# Calciatore_Rev_2_UP.net
KiCad netlist of a schematic drawn in EAGLE
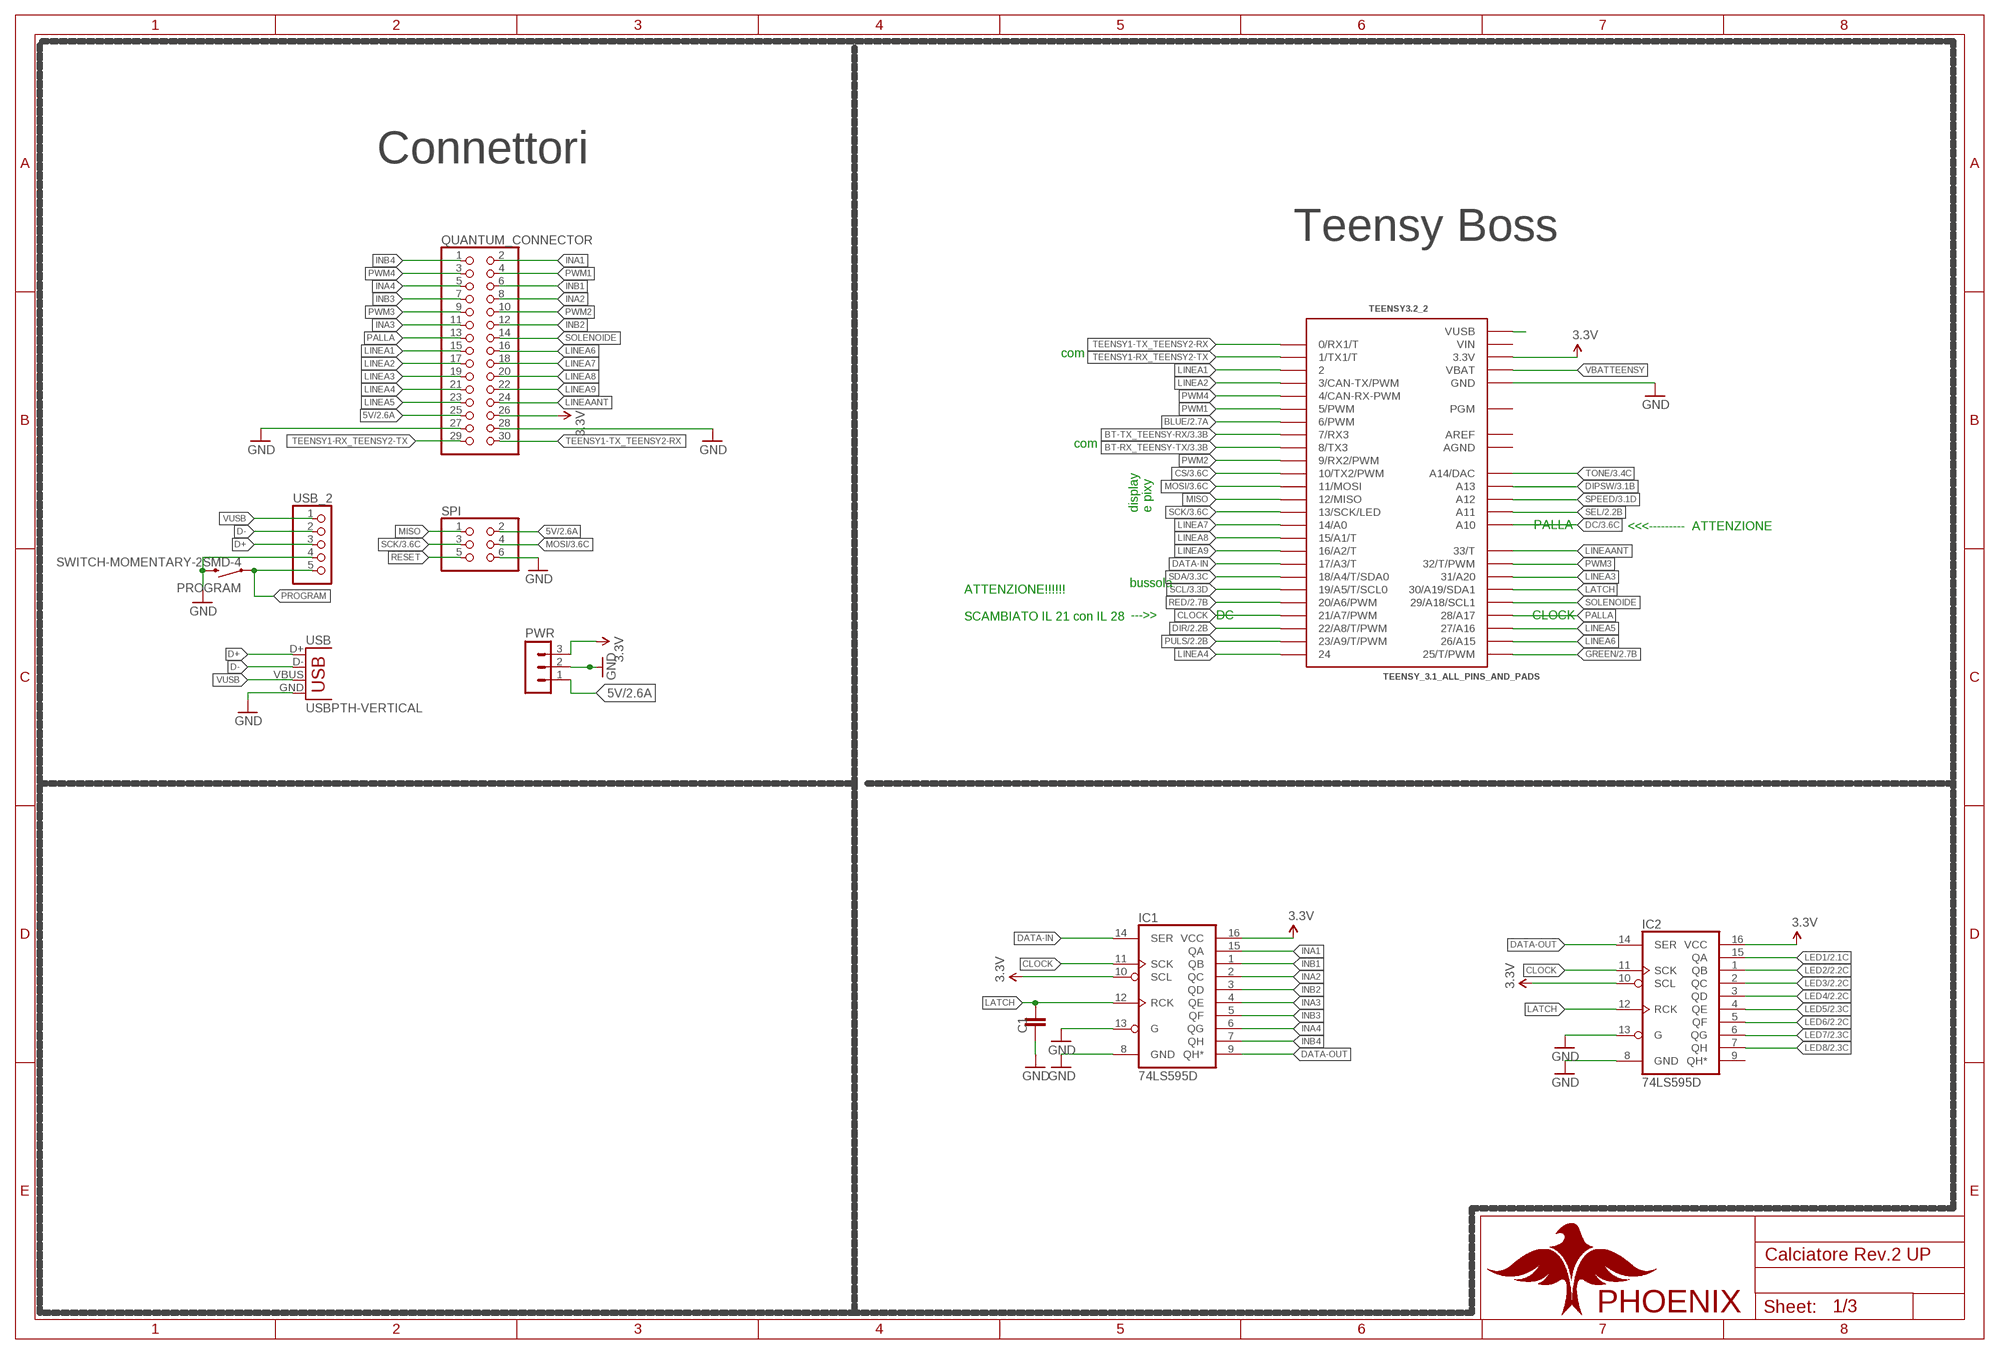
[diagram p0: schematic, sheet 1]
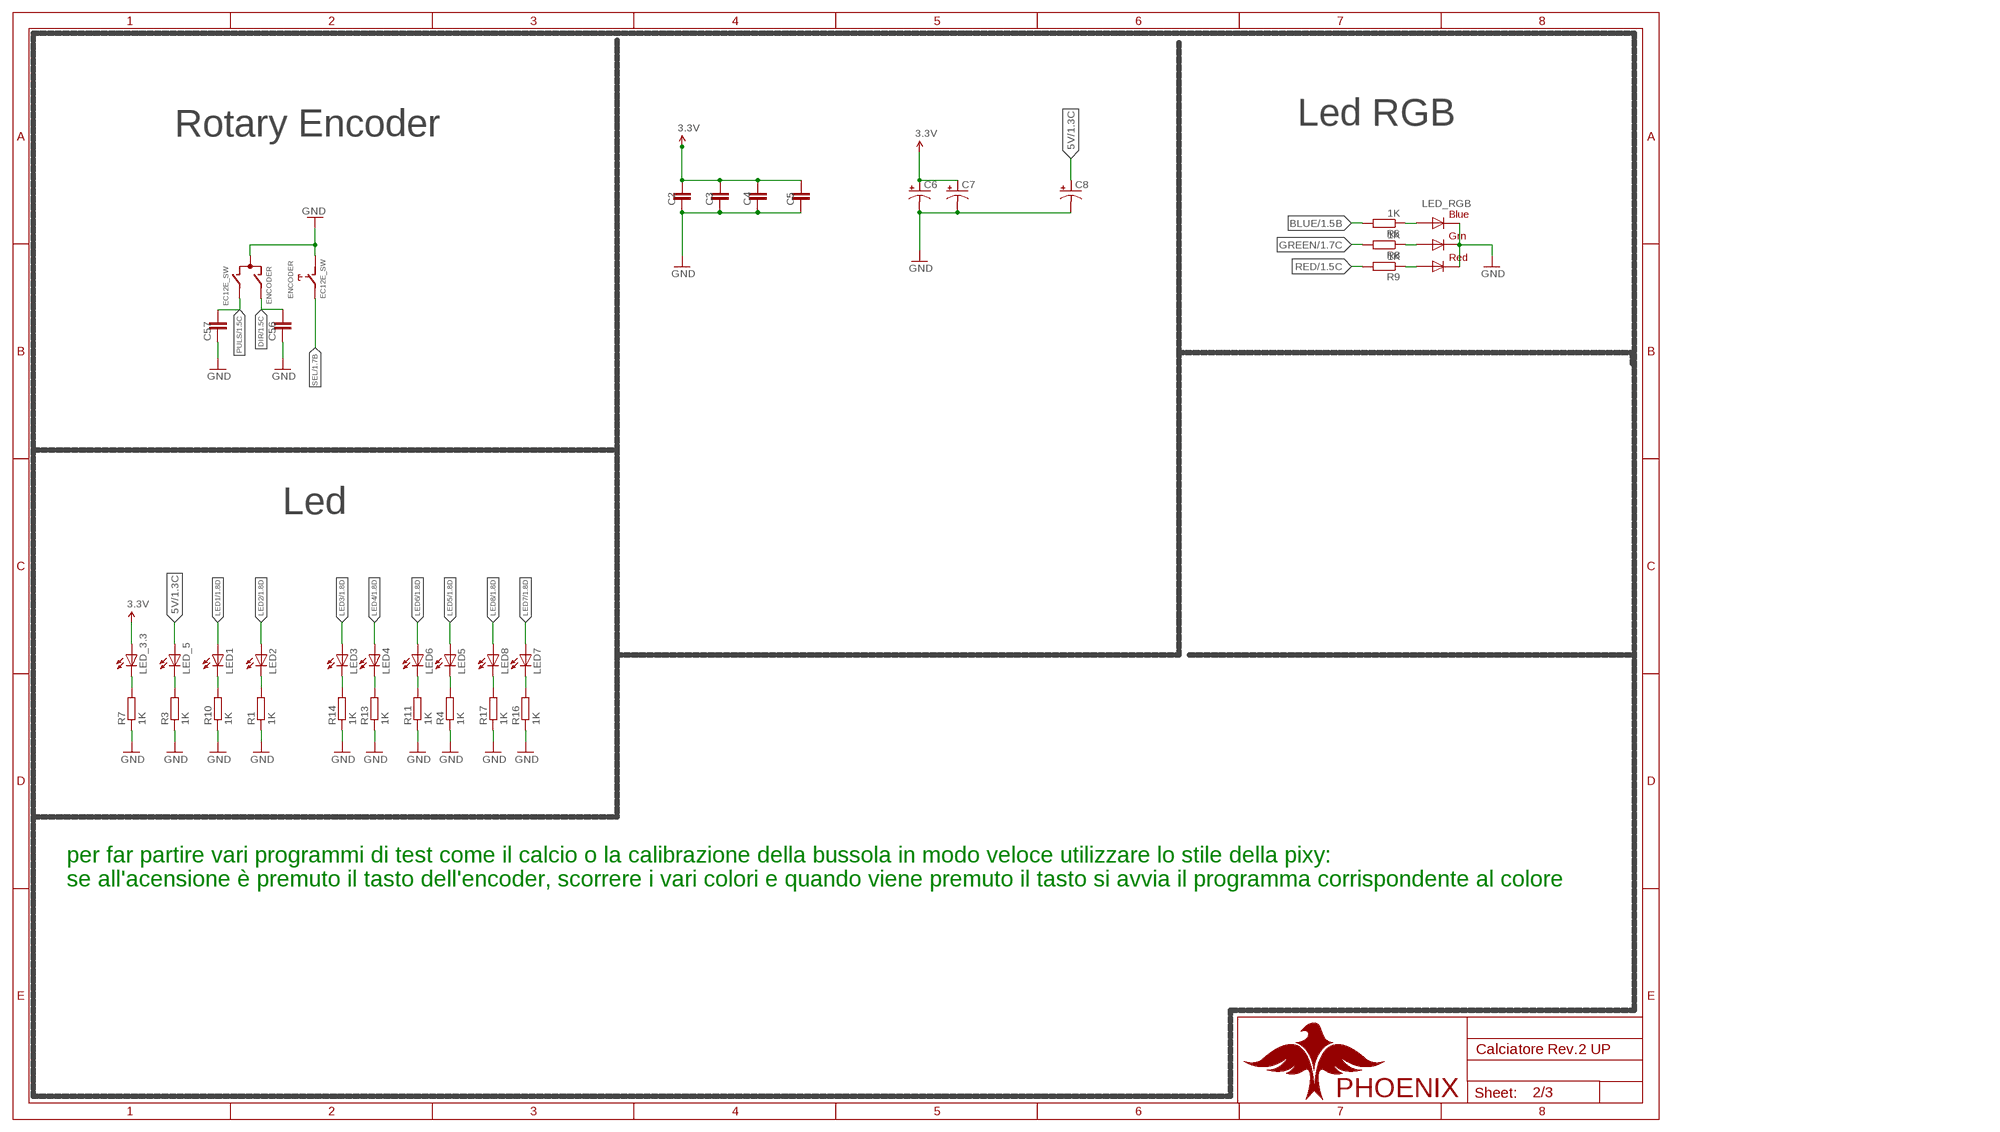
[diagram p1: schematic, sheet 2]
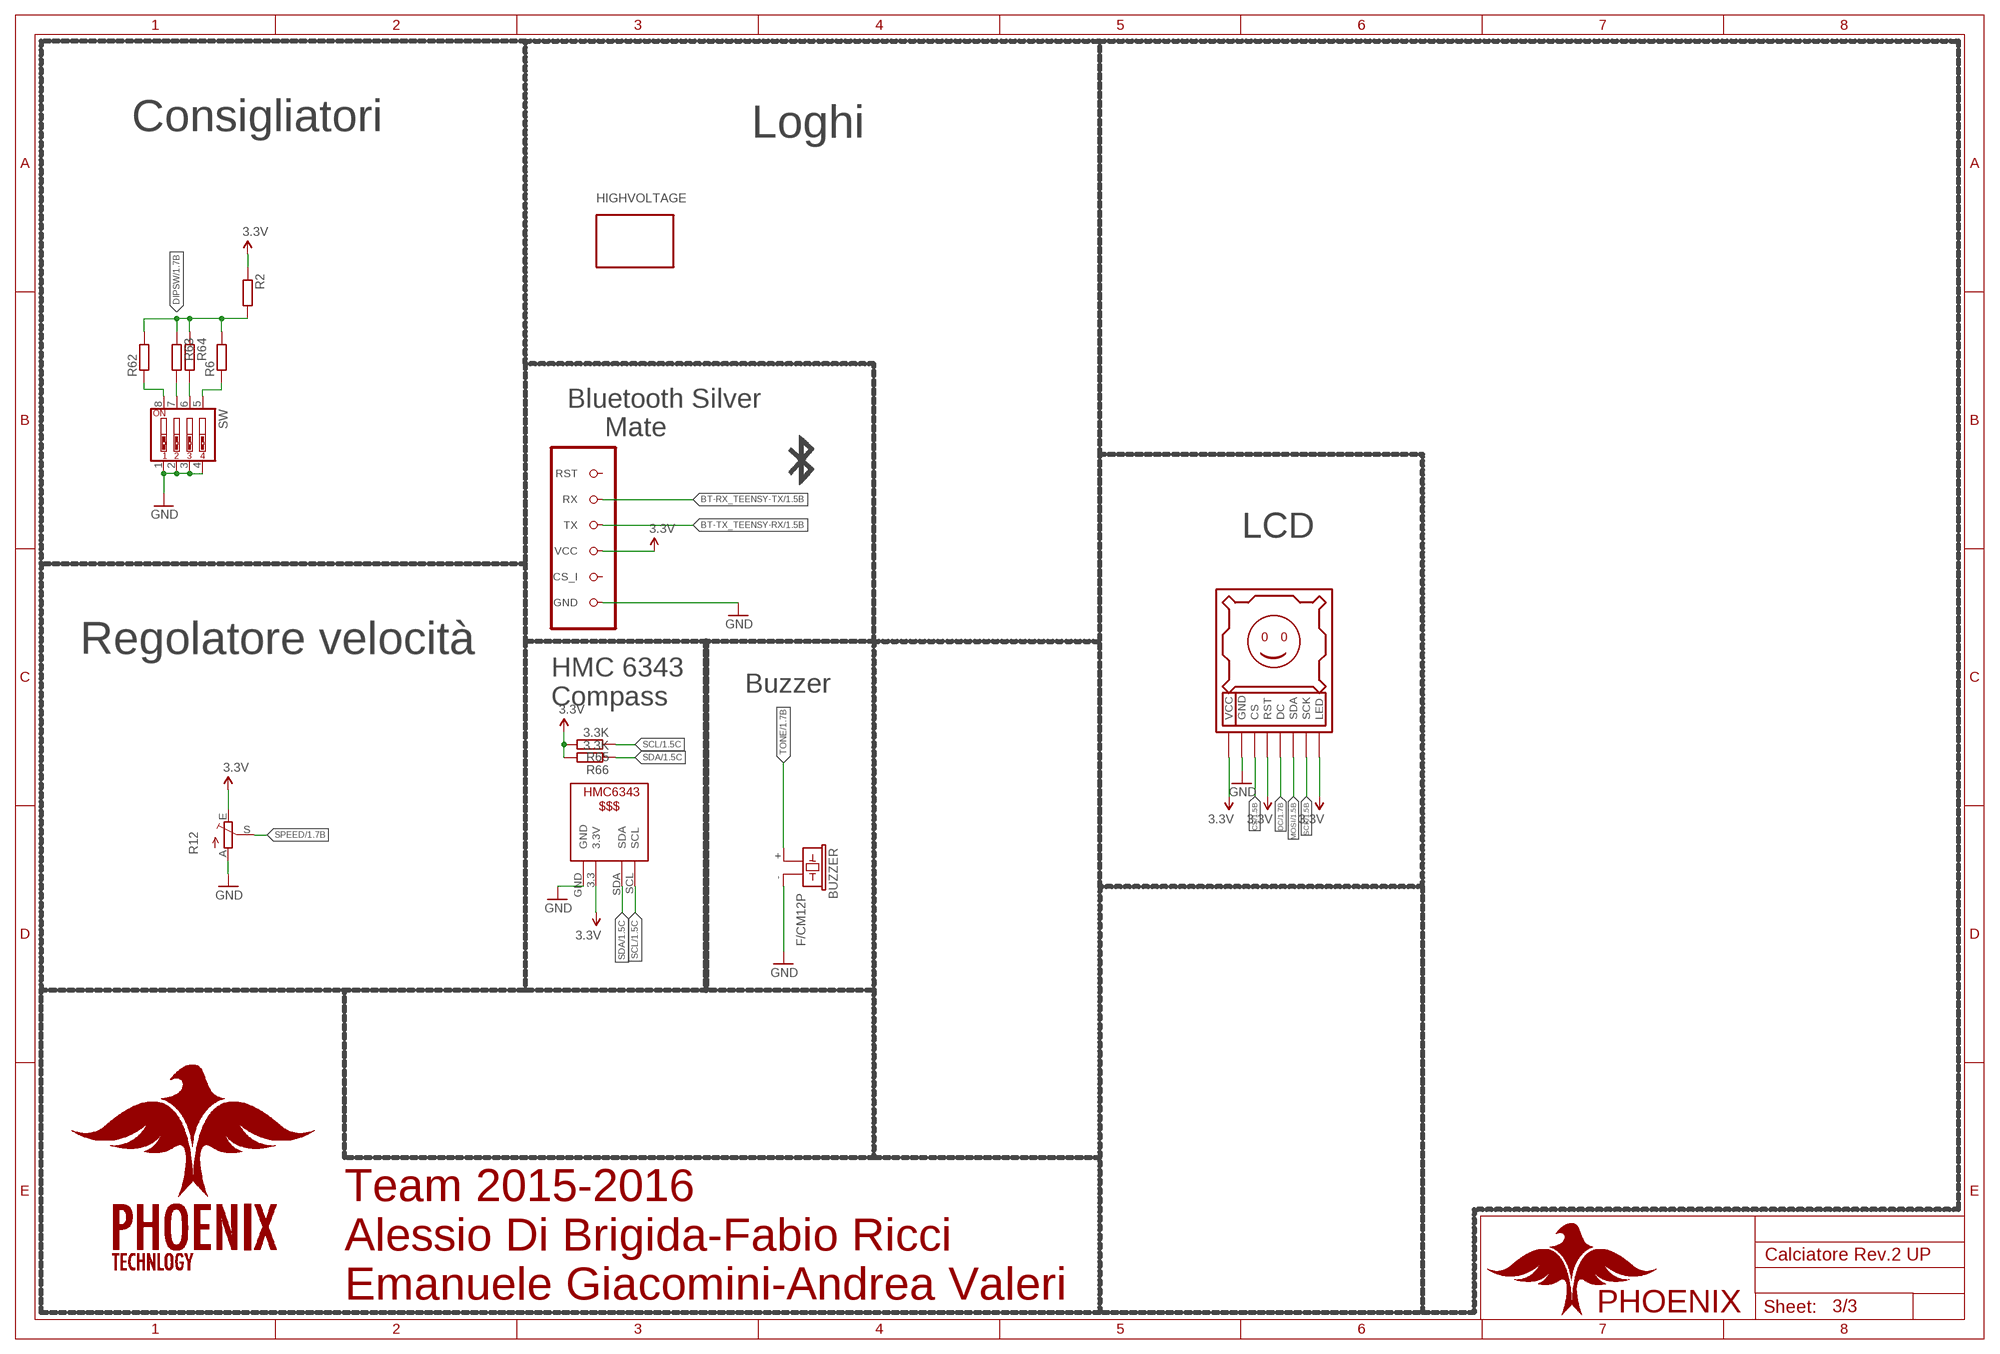
[diagram p2: schematic, sheet 3]

(export (version "E")
  (design (tool "Eeschema 10.0.6"))
  (components
    (comp (ref "C2")
      (value "C-EUC1206")
      (footprint "eagle-import:C1206")
      (libsource (lib "eagle-import") (part "C-EUC1206"))
    )
    (comp (ref "C3")
      (value "C-EUC1206")
      (footprint "eagle-import:C1206")
      (libsource (lib "eagle-import") (part "C-EUC1206"))
    )
    (comp (ref "C4")
      (value "C-EUC1206")
      (footprint "eagle-import:C1206")
      (libsource (lib "eagle-import") (part "C-EUC1206"))
    )
    (comp (ref "C5")
      (value "C-EUC1206")
      (footprint "eagle-import:C1206")
      (libsource (lib "eagle-import") (part "C-EUC1206"))
    )
    (comp (ref "C6")
      (value "CPOL-USE3.5-8")
      (footprint "eagle-import:E3,5-8")
      (libsource (lib "eagle-import") (part "CPOL-USE3.5-8"))
    )
    (comp (ref "C7")
      (value "CPOL-USE3.5-8")
      (footprint "eagle-import:E3,5-8")
      (libsource (lib "eagle-import") (part "CPOL-USE3.5-8"))
    )
    (comp (ref "C8")
      (value "CPOL-USE3.5-8")
      (footprint "eagle-import:E3,5-8")
      (libsource (lib "eagle-import") (part "CPOL-USE3.5-8"))
    )
    (comp (ref "C56")
      (value "C-EUC1206")
      (footprint "eagle-import:C1206")
      (libsource (lib "eagle-import") (part "C-EUC1206"))
    )
    (comp (ref "C57")
      (value "C-EUC1206")
      (footprint "eagle-import:C1206")
      (libsource (lib "eagle-import") (part "C-EUC1206"))
    )
    (comp (ref "ENCODER")
      (value "EC12E_SW")
      (footprint "eagle-import:ALPS_EC12E_SW")
      (fields (field (name "MPN") "EC12E2424407"))
      (libsource (lib "eagle-import") (part "EC12E_SW"))
    )
    (comp (ref "LED1")
      (value "LEDSMT1206")
      (footprint "eagle-import:1206")
      (libsource (lib "eagle-import") (part "LEDSMT1206"))
    )
    (comp (ref "LED2")
      (value "LEDSMT1206")
      (footprint "eagle-import:1206")
      (libsource (lib "eagle-import") (part "LEDSMT1206"))
    )
    (comp (ref "LED3")
      (value "LEDSMT1206")
      (footprint "eagle-import:1206")
      (libsource (lib "eagle-import") (part "LEDSMT1206"))
    )
    (comp (ref "LED4")
      (value "LEDSMT1206")
      (footprint "eagle-import:1206")
      (libsource (lib "eagle-import") (part "LEDSMT1206"))
    )
    (comp (ref "LED5")
      (value "LEDSMT1206")
      (footprint "eagle-import:1206")
      (libsource (lib "eagle-import") (part "LEDSMT1206"))
    )
    (comp (ref "LED6")
      (value "LEDSMT1206")
      (footprint "eagle-import:1206")
      (libsource (lib "eagle-import") (part "LEDSMT1206"))
    )
    (comp (ref "LED7")
      (value "LEDSMT1206")
      (footprint "eagle-import:1206")
      (libsource (lib "eagle-import") (part "LEDSMT1206"))
    )
    (comp (ref "LED8")
      (value "LEDSMT1206")
      (footprint "eagle-import:1206")
      (libsource (lib "eagle-import") (part "LEDSMT1206"))
    )
    (comp (ref "LED_3.3")
      (value "LEDSMT1206")
      (footprint "eagle-import:1206")
      (libsource (lib "eagle-import") (part "LEDSMT1206"))
    )
    (comp (ref "LED_5")
      (value "LEDSMT1206")
      (footprint "eagle-import:1206")
      (libsource (lib "eagle-import") (part "LEDSMT1206"))
    )
    (comp (ref "LED_RGB")
      (value "RGBLED5050")
      (footprint "eagle-import:RGBLED5050")
      (libsource (lib "eagle-import") (part "RGBLED5050"))
    )
    (comp (ref "R1")
      (value "1K")
      (footprint "eagle-import:M1206")
      (libsource (lib "eagle-import") (part "resistor_R-EU_M1206"))
    )
    (comp (ref "R3")
      (value "1K")
      (footprint "eagle-import:M1206")
      (libsource (lib "eagle-import") (part "resistor_R-EU_M1206"))
    )
    (comp (ref "R4")
      (value "1K")
      (footprint "eagle-import:M1206")
      (libsource (lib "eagle-import") (part "resistor_R-EU_M1206"))
    )
    (comp (ref "R5")
      (value "1K")
      (footprint "eagle-import:M1206")
      (libsource (lib "eagle-import") (part "resistor_R-EU_M1206"))
    )
    (comp (ref "R7")
      (value "1K")
      (footprint "eagle-import:M1206")
      (libsource (lib "eagle-import") (part "resistor_R-EU_M1206"))
    )
    (comp (ref "R8")
      (value "1K")
      (footprint "eagle-import:M1206")
      (libsource (lib "eagle-import") (part "resistor_R-EU_M1206"))
    )
    (comp (ref "R9")
      (value "1K")
      (footprint "eagle-import:M1206")
      (libsource (lib "eagle-import") (part "resistor_R-EU_M1206"))
    )
    (comp (ref "R10")
      (value "1K")
      (footprint "eagle-import:M1206")
      (libsource (lib "eagle-import") (part "resistor_R-EU_M1206"))
    )
    (comp (ref "R11")
      (value "1K")
      (footprint "eagle-import:M1206")
      (libsource (lib "eagle-import") (part "resistor_R-EU_M1206"))
    )
    (comp (ref "R13")
      (value "1K")
      (footprint "eagle-import:M1206")
      (libsource (lib "eagle-import") (part "resistor_R-EU_M1206"))
    )
    (comp (ref "R14")
      (value "1K")
      (footprint "eagle-import:M1206")
      (libsource (lib "eagle-import") (part "resistor_R-EU_M1206"))
    )
    (comp (ref "R16")
      (value "1K")
      (footprint "eagle-import:M1206")
      (libsource (lib "eagle-import") (part "resistor_R-EU_M1206"))
    )
    (comp (ref "R17")
      (value "1K")
      (footprint "eagle-import:M1206")
      (libsource (lib "eagle-import") (part "resistor_R-EU_M1206"))
    )
    (comp (ref "BUZZER")
      (value "F/CM12P")
      (footprint "eagle-import:F_CM12P")
      (libsource (lib "eagle-import") (part "F/CM12P"))
    )
    (comp (ref "DISPLAY1")
      (value "DISPLAY128X128")
      (footprint "eagle-import:DISPLAY128X128")
      (libsource (lib "eagle-import") (part "DISPLAY128X128"))
    )
    (comp (ref "HIGHVOLTAGE")
      (value "LOGO")
      (footprint "eagle-import:LOGOHV")
      (libsource (lib "eagle-import") (part "LOGO"))
    )
    (comp (ref "R2")
      (value "10K")
      (footprint "eagle-import:M1206")
      (libsource (lib "eagle-import") (part "R-EU_M1206"))
    )
    (comp (ref "R6")
      (value "10K")
      (footprint "eagle-import:M1206")
      (libsource (lib "eagle-import") (part "R-EU_M1206"))
    )
    (comp (ref "R12")
      (value "TRIM_EU-S63P")
      (footprint "eagle-import:S63P")
      (libsource (lib "eagle-import") (part "TRIM_EU-S63P"))
    )
    (comp (ref "R62")
      (value "10K")
      (footprint "eagle-import:M1206")
      (libsource (lib "eagle-import") (part "R-EU_M1206"))
    )
    (comp (ref "R63")
      (value "10K")
      (footprint "eagle-import:M1206")
      (libsource (lib "eagle-import") (part "R-EU_M1206"))
    )
    (comp (ref "R64")
      (value "10K")
      (footprint "eagle-import:M1206")
      (libsource (lib "eagle-import") (part "R-EU_M1206"))
    )
    (comp (ref "R65")
      (value "3.3K")
      (footprint "eagle-import:M1206")
      (libsource (lib "eagle-import") (part "R-EU_M1206"))
    )
    (comp (ref "R66")
      (value "3.3K")
      (footprint "eagle-import:M1206")
      (libsource (lib "eagle-import") (part "R-EU_M1206"))
    )
    (comp (ref "SW")
      (value "SW_DIP-4")
      (footprint "eagle-import:EDG-04")
      (libsource (lib "eagle-import") (part "SW_DIP-4"))
    )
    (comp (ref "U$5")
      (value "HMC6343")
      (footprint "eagle-import:HMC6343")
      (libsource (lib "eagle-import") (part "HMC6343"))
    )
    (comp (ref "U$9")
      (value "BLUETOOTH")
      (footprint "eagle-import:BLUETOOTH")
      (libsource (lib "eagle-import") (part "BLUETOOTH"))
    )
    (comp (ref "C1")
      (value "C-EUC1206")
      (footprint "eagle-import:C1206")
      (libsource (lib "eagle-import") (part "C-EUC1206"))
    )
    (comp (ref "IC1")
      (value "74LS595D")
      (footprint "eagle-import:SO16")
      (libsource (lib "eagle-import") (part "74595DLS"))
    )
    (comp (ref "IC2")
      (value "74LS595D")
      (footprint "eagle-import:SO16")
      (libsource (lib "eagle-import") (part "74595DLS"))
    )
    (comp (ref "PROGRAM")
      (value "SWITCH-MOMENTARY-2SMD-4")
      (footprint "eagle-import:TACTILE_SWITCH_TALL")
      (libsource (lib "eagle-import") (part "SWITCH-MOMENTARY-2SMD-4"))
    )
    (comp (ref "PWR")
      (value "MA03-1")
      (footprint "eagle-import:MA03-1")
      (libsource (lib "eagle-import") (part "MA03-1"))
    )
    (comp (ref "QUANTUM_CONNECTOR")
      (value "PINHD-2X15")
      (footprint "eagle-import:2X15")
      (libsource (lib "eagle-import") (part "PINHD-2X15"))
    )
    (comp (ref "SPI")
      (value "PINHD-2X3")
      (footprint "eagle-import:2X03")
      (libsource (lib "eagle-import") (part "PINHD-2X3"))
    )
    (comp (ref "TEENSY3.2_2")
      (value "TEENSY_3.1_ALL_PINS_AND_PADS")
      (footprint "eagle-import:TEENSY3_ALL_PINS_&_PADS")
      (libsource (lib "eagle-import") (part "TEENSY_3.1_ALL_PINS_AND_PADS"))
    )
    (comp (ref "USB")
      (value "USBPTH-VERTICAL")
      (footprint "eagle-import:USB-B-PTH-VERTICAL")
      (libsource (lib "eagle-import") (part "USBPTH-VERTICAL"))
    )
    (comp (ref "USB_2")
      (value "PINHD-1X5")
      (footprint "eagle-import:1X05")
      (libsource (lib "eagle-import") (part "PINHD-1X5"))
    )
  )
  (nets
    (net (code "1") (name "3.3V") (class "Default")
      (node (ref "C2") (pin "2") (pinfunction "2_2") (pintype "passive"))
      (node (ref "C3") (pin "2") (pinfunction "2_2") (pintype "passive"))
      (node (ref "C4") (pin "2") (pinfunction "2_2") (pintype "passive"))
      (node (ref "C5") (pin "2") (pinfunction "2_2") (pintype "passive"))
      (node (ref "C6") (pin "+") (pinfunction "+_+") (pintype "passive"))
      (node (ref "C7") (pin "+") (pinfunction "+_+") (pintype "passive"))
      (node (ref "DISPLAY1") (pin "LED") (pinfunction "LED_LED") (pintype "input"))
      (node (ref "DISPLAY1") (pin "RST") (pinfunction "RST_RST") (pintype "input"))
      (node (ref "DISPLAY1") (pin "VCC") (pinfunction "VCC_VCC") (pintype "power_in"))
      (node (ref "IC1") (pin "10") (pinfunction "SCL_10") (pintype "input"))
      (node (ref "IC1") (pin "16") (pinfunction "VCC_16") (pintype "power_in"))
      (node (ref "IC2") (pin "10") (pinfunction "SCL_10") (pintype "input"))
      (node (ref "IC2") (pin "16") (pinfunction "VCC_16") (pintype "power_in"))
      (node (ref "LED_3.3") (pin "A") (pinfunction "A_A") (pintype "passive"))
      (node (ref "PWR") (pin "3") (pinfunction "3_3") (pintype "passive"))
      (node (ref "QUANTUM_CONNECTOR") (pin "26") (pinfunction "26_26") (pintype "passive"))
      (node (ref "R12") (pin "E") (pinfunction "E_E") (pintype "passive"))
      (node (ref "R2") (pin "1") (pinfunction "1_1") (pintype "passive"))
      (node (ref "R65") (pin "2") (pinfunction "2_2") (pintype "passive"))
      (node (ref "R66") (pin "2") (pinfunction "2_2") (pintype "passive"))
      (node (ref "TEENSY3.2_2") (pin "3.3V") (pinfunction "3.3V_3.3V") (pintype "power_in"))
      (node (ref "TEENSY3.2_2") (pin "3.3V1") (pinfunction "3.3V_3.3V1") (pintype "power_in"))
      (node (ref "TEENSY3.2_2") (pin "3.3V2") (pinfunction "3.3V_3.3V2") (pintype "power_in"))
      (node (ref "U$5") (pin "3.3") (pinfunction "3.3V_3.3") (pintype "bidirectional"))
      (node (ref "U$9") (pin "VCC") (pinfunction "VCC_VCC") (pintype "power_in"))
    )
    (net (code "2") (name "5V") (class "Default")
      (node (ref "C8") (pin "+") (pinfunction "+_+") (pintype "passive"))
      (node (ref "LED_5") (pin "A") (pinfunction "A_A") (pintype "passive"))
      (node (ref "PWR") (pin "1") (pinfunction "1_1") (pintype "passive"))
      (node (ref "QUANTUM_CONNECTOR") (pin "25") (pinfunction "25_25") (pintype "passive"))
      (node (ref "SPI") (pin "2") (pinfunction "2_2") (pintype "passive"))
    )
    (net (code "3") (name "AGND") (class "Default")
      (node (ref "TEENSY3.2_2") (pin "AGND") (pinfunction "AGND_AGND") (pintype "power_in"))
    )
    (net (code "4") (name "AREF") (class "Default")
      (node (ref "TEENSY3.2_2") (pin "AREF") (pinfunction "AREF_AREF") (pintype "power_in"))
    )
    (net (code "5") (name "BLUE") (class "Default")
      (node (ref "R5") (pin "2") (pinfunction "2_2") (pintype "passive"))
      (node (ref "TEENSY3.2_2") (pin "6") (pinfunction "6/PWM_6") (pintype "bidirectional"))
    )
    (net (code "6") (name "BT-RX_TEENSY-TX") (class "Default")
      (node (ref "TEENSY3.2_2") (pin "8") (pinfunction "8/TX3_8") (pintype "bidirectional"))
      (node (ref "U$9") (pin "RX") (pinfunction "RX_RX") (pintype "input"))
    )
    (net (code "7") (name "BT-TX_TEENSY-RX") (class "Default")
      (node (ref "TEENSY3.2_2") (pin "7") (pinfunction "7/RX3_7") (pintype "bidirectional"))
      (node (ref "U$9") (pin "TX") (pinfunction "TX_TX") (pintype "output"))
    )
    (net (code "8") (name "CLOCK") (class "Default")
      (node (ref "IC1") (pin "11") (pinfunction "SCK_11") (pintype "input"))
      (node (ref "IC2") (pin "11") (pinfunction "SCK_11") (pintype "input"))
      (node (ref "TEENSY3.2_2") (pin "21/A7") (pinfunction "21/A7/PWM_21/A7") (pintype "bidirectional"))
    )
    (net (code "9") (name "CS") (class "Default")
      (node (ref "DISPLAY1") (pin "CS") (pinfunction "CS_CS") (pintype "bidirectional"))
      (node (ref "TEENSY3.2_2") (pin "10") (pinfunction "10/TX2/PWM_10") (pintype "bidirectional"))
    )
    (net (code "10") (name "D+") (class "Default")
      (node (ref "USB") (pin "D+") (pinfunction "D+_D+") (pintype "bidirectional"))
      (node (ref "USB_2") (pin "3") (pinfunction "3_3") (pintype "passive"))
    )
    (net (code "11") (name "D-") (class "Default")
      (node (ref "USB") (pin "D-") (pinfunction "D-_D-") (pintype "bidirectional"))
      (node (ref "USB_2") (pin "2") (pinfunction "2_2") (pintype "passive"))
    )
    (net (code "12") (name "DATA-IN") (class "Default")
      (node (ref "IC1") (pin "14") (pinfunction "SER_14") (pintype "input"))
      (node (ref "TEENSY3.2_2") (pin "17/A3") (pinfunction "17/A3/T_17/A3") (pintype "bidirectional"))
    )
    (net (code "13") (name "DATA-OUT") (class "Default")
      (node (ref "IC1") (pin "9") (pinfunction "QH*_9") (pintype "tri_state"))
      (node (ref "IC2") (pin "14") (pinfunction "SER_14") (pintype "input"))
    )
    (net (code "14") (name "DC") (class "Default")
      (node (ref "DISPLAY1") (pin "DC") (pinfunction "DC_DC") (pintype "bidirectional"))
      (node (ref "TEENSY3.2_2") (pin "A10") (pinfunction "A10_A10") (pintype "bidirectional"))
    )
    (net (code "15") (name "DIPSW") (class "Default")
      (node (ref "R2") (pin "2") (pinfunction "2_2") (pintype "passive"))
      (node (ref "R6") (pin "2") (pinfunction "2_2") (pintype "passive"))
      (node (ref "R62") (pin "2") (pinfunction "2_2") (pintype "passive"))
      (node (ref "R63") (pin "1") (pinfunction "1_1") (pintype "passive"))
      (node (ref "R64") (pin "1") (pinfunction "1_1") (pintype "passive"))
      (node (ref "TEENSY3.2_2") (pin "A13") (pinfunction "A13_A13") (pintype "bidirectional"))
    )
    (net (code "16") (name "DIR") (class "Default")
      (node (ref "C56") (pin "2") (pinfunction "2_2") (pintype "passive"))
      (node (ref "ENCODER") (pin "A") (pinfunction "A_A") (pintype "passive"))
      (node (ref "TEENSY3.2_2") (pin "22/A8") (pinfunction "22/A8/T/PWM_22/A8") (pintype "bidirectional"))
    )
    (net (code "17") (name "GND") (class "Default")
      (node (ref "BUZZER") (pin "-") (pinfunction "2_-") (pintype "passive"))
      (node (ref "C1") (pin "1") (pinfunction "1_1") (pintype "passive"))
      (node (ref "C2") (pin "1") (pinfunction "1_1") (pintype "passive"))
      (node (ref "C3") (pin "1") (pinfunction "1_1") (pintype "passive"))
      (node (ref "C4") (pin "1") (pinfunction "1_1") (pintype "passive"))
      (node (ref "C5") (pin "1") (pinfunction "1_1") (pintype "passive"))
      (node (ref "C56") (pin "1") (pinfunction "1_1") (pintype "passive"))
      (node (ref "C57") (pin "1") (pinfunction "1_1") (pintype "passive"))
      (node (ref "C6") (pin "-") (pinfunction "-_-") (pintype "passive"))
      (node (ref "C7") (pin "-") (pinfunction "-_-") (pintype "passive"))
      (node (ref "C8") (pin "-") (pinfunction "-_-") (pintype "passive"))
      (node (ref "DISPLAY1") (pin "GND") (pinfunction "GND_GND") (pintype "power_in"))
      (node (ref "ENCODER") (pin "C") (pinfunction "C_C") (pintype "passive"))
      (node (ref "ENCODER") (pin "D") (pinfunction "1_D") (pintype "passive"))
      (node (ref "IC1") (pin "13") (pinfunction "G_13") (pintype "input"))
      (node (ref "IC1") (pin "8") (pinfunction "GND_8") (pintype "power_in"))
      (node (ref "IC2") (pin "13") (pinfunction "G_13") (pintype "input"))
      (node (ref "IC2") (pin "8") (pinfunction "GND_8") (pintype "power_in"))
      (node (ref "LED_RGB") (pin "4") (pinfunction "BLUE_C_4") (pintype "bidirectional"))
      (node (ref "LED_RGB") (pin "5") (pinfunction "RED_C_5") (pintype "bidirectional"))
      (node (ref "LED_RGB") (pin "6") (pinfunction "GREEN_C_6") (pintype "bidirectional"))
      (node (ref "PROGRAM") (pin "B2") (pinfunction "2_B2") (pintype "passive"))
      (node (ref "PWR") (pin "2") (pinfunction "2_2") (pintype "passive"))
      (node (ref "QUANTUM_CONNECTOR") (pin "27") (pinfunction "27_27") (pintype "passive"))
      (node (ref "QUANTUM_CONNECTOR") (pin "28") (pinfunction "28_28") (pintype "passive"))
      (node (ref "R1") (pin "1") (pinfunction "1_1") (pintype "passive"))
      (node (ref "R10") (pin "1") (pinfunction "1_1") (pintype "passive"))
      (node (ref "R11") (pin "1") (pinfunction "1_1") (pintype "passive"))
      (node (ref "R12") (pin "A") (pinfunction "A_A") (pintype "passive"))
      (node (ref "R13") (pin "1") (pinfunction "1_1") (pintype "passive"))
      (node (ref "R14") (pin "1") (pinfunction "1_1") (pintype "passive"))
      (node (ref "R16") (pin "1") (pinfunction "1_1") (pintype "passive"))
      (node (ref "R17") (pin "1") (pinfunction "1_1") (pintype "passive"))
      (node (ref "R3") (pin "1") (pinfunction "1_1") (pintype "passive"))
      (node (ref "R4") (pin "1") (pinfunction "1_1") (pintype "passive"))
      (node (ref "R7") (pin "1") (pinfunction "1_1") (pintype "passive"))
      (node (ref "SPI") (pin "6") (pinfunction "6_6") (pintype "passive"))
      (node (ref "SW") (pin "1") (pinfunction "1_1") (pintype "passive"))
      (node (ref "SW") (pin "2") (pinfunction "2_2") (pintype "passive"))
      (node (ref "SW") (pin "3") (pinfunction "3_3") (pintype "passive"))
      (node (ref "SW") (pin "4") (pinfunction "4_4") (pintype "passive"))
      (node (ref "TEENSY3.2_2") (pin "GND") (pinfunction "GND_GND") (pintype "power_in"))
      (node (ref "TEENSY3.2_2") (pin "GND1") (pinfunction "GND_GND1") (pintype "power_in"))
      (node (ref "TEENSY3.2_2") (pin "GND2") (pinfunction "GND_GND2") (pintype "power_in"))
      (node (ref "U$5") (pin "GND") (pinfunction "GND_GND") (pintype "bidirectional"))
      (node (ref "U$9") (pin "GND") (pinfunction "GND_GND") (pintype "power_in"))
      (node (ref "USB") (pin "GND") (pinfunction "GND_GND") (pintype "bidirectional"))
      (node (ref "USB_2") (pin "4") (pinfunction "4_4") (pintype "passive"))
    )
    (net (code "18") (name "GREEN") (class "Default")
      (node (ref "R8") (pin "2") (pinfunction "2_2") (pintype "passive"))
      (node (ref "TEENSY3.2_2") (pin "25") (pinfunction "25/T/PWM_25") (pintype "bidirectional"))
    )
    (net (code "19") (name "INA1") (class "Default")
      (node (ref "IC1") (pin "15") (pinfunction "QA_15") (pintype "tri_state"))
      (node (ref "QUANTUM_CONNECTOR") (pin "2") (pinfunction "2_2") (pintype "passive"))
    )
    (net (code "20") (name "INA2") (class "Default")
      (node (ref "IC1") (pin "2") (pinfunction "QC_2") (pintype "tri_state"))
      (node (ref "QUANTUM_CONNECTOR") (pin "8") (pinfunction "8_8") (pintype "passive"))
    )
    (net (code "21") (name "INA3") (class "Default")
      (node (ref "IC1") (pin "4") (pinfunction "QE_4") (pintype "tri_state"))
      (node (ref "QUANTUM_CONNECTOR") (pin "11") (pinfunction "11_11") (pintype "passive"))
    )
    (net (code "22") (name "INA4") (class "Default")
      (node (ref "IC1") (pin "6") (pinfunction "QG_6") (pintype "tri_state"))
      (node (ref "QUANTUM_CONNECTOR") (pin "5") (pinfunction "5_5") (pintype "passive"))
    )
    (net (code "23") (name "INB1") (class "Default")
      (node (ref "IC1") (pin "1") (pinfunction "QB_1") (pintype "tri_state"))
      (node (ref "QUANTUM_CONNECTOR") (pin "6") (pinfunction "6_6") (pintype "passive"))
    )
    (net (code "24") (name "INB2") (class "Default")
      (node (ref "IC1") (pin "3") (pinfunction "QD_3") (pintype "tri_state"))
      (node (ref "QUANTUM_CONNECTOR") (pin "12") (pinfunction "12_12") (pintype "passive"))
    )
    (net (code "25") (name "INB3") (class "Default")
      (node (ref "IC1") (pin "5") (pinfunction "QF_5") (pintype "tri_state"))
      (node (ref "QUANTUM_CONNECTOR") (pin "7") (pinfunction "7_7") (pintype "passive"))
    )
    (net (code "26") (name "INB4") (class "Default")
      (node (ref "IC1") (pin "7") (pinfunction "QH_7") (pintype "tri_state"))
      (node (ref "QUANTUM_CONNECTOR") (pin "1") (pinfunction "1_1") (pintype "passive"))
    )
    (net (code "27") (name "LATCH") (class "Default")
      (node (ref "C1") (pin "2") (pinfunction "2_2") (pintype "passive"))
      (node (ref "IC1") (pin "12") (pinfunction "RCK_12") (pintype "input"))
      (node (ref "IC2") (pin "12") (pinfunction "RCK_12") (pintype "input"))
      (node (ref "TEENSY3.2_2") (pin "30") (pinfunction "30/A19/SDA1_30") (pintype "bidirectional"))
    )
    (net (code "28") (name "LED1") (class "Default")
      (node (ref "IC2") (pin "15") (pinfunction "QA_15") (pintype "tri_state"))
      (node (ref "LED1") (pin "A") (pinfunction "A_A") (pintype "passive"))
    )
    (net (code "29") (name "LED2") (class "Default")
      (node (ref "IC2") (pin "1") (pinfunction "QB_1") (pintype "tri_state"))
      (node (ref "LED2") (pin "A") (pinfunction "A_A") (pintype "passive"))
    )
    (net (code "30") (name "LED3") (class "Default")
      (node (ref "IC2") (pin "2") (pinfunction "QC_2") (pintype "tri_state"))
      (node (ref "LED3") (pin "A") (pinfunction "A_A") (pintype "passive"))
    )
    (net (code "31") (name "LED4") (class "Default")
      (node (ref "IC2") (pin "3") (pinfunction "QD_3") (pintype "tri_state"))
      (node (ref "LED4") (pin "A") (pinfunction "A_A") (pintype "passive"))
    )
    (net (code "32") (name "LED5") (class "Default")
      (node (ref "IC2") (pin "4") (pinfunction "QE_4") (pintype "tri_state"))
      (node (ref "LED5") (pin "A") (pinfunction "A_A") (pintype "passive"))
    )
    (net (code "33") (name "LED6") (class "Default")
      (node (ref "IC2") (pin "5") (pinfunction "QF_5") (pintype "tri_state"))
      (node (ref "LED6") (pin "A") (pinfunction "A_A") (pintype "passive"))
    )
    (net (code "34") (name "LED7") (class "Default")
      (node (ref "IC2") (pin "6") (pinfunction "QG_6") (pintype "tri_state"))
      (node (ref "LED7") (pin "A") (pinfunction "A_A") (pintype "passive"))
    )
    (net (code "35") (name "LED8") (class "Default")
      (node (ref "IC2") (pin "7") (pinfunction "QH_7") (pintype "tri_state"))
      (node (ref "LED8") (pin "A") (pinfunction "A_A") (pintype "passive"))
    )
    (net (code "36") (name "LINEA1") (class "Default")
      (node (ref "QUANTUM_CONNECTOR") (pin "15") (pinfunction "15_15") (pintype "passive"))
      (node (ref "TEENSY3.2_2") (pin "2") (pinfunction "2_2") (pintype "bidirectional"))
    )
    (net (code "37") (name "LINEA2") (class "Default")
      (node (ref "QUANTUM_CONNECTOR") (pin "17") (pinfunction "17_17") (pintype "passive"))
      (node (ref "TEENSY3.2_2") (pin "3") (pinfunction "3/CAN-TX/PWM_3") (pintype "bidirectional"))
    )
    (net (code "38") (name "LINEA3") (class "Default")
      (node (ref "QUANTUM_CONNECTOR") (pin "19") (pinfunction "19_19") (pintype "passive"))
      (node (ref "TEENSY3.2_2") (pin "31") (pinfunction "31/A20_31") (pintype "bidirectional"))
    )
    (net (code "39") (name "LINEA4") (class "Default")
      (node (ref "QUANTUM_CONNECTOR") (pin "21") (pinfunction "21_21") (pintype "passive"))
      (node (ref "TEENSY3.2_2") (pin "24") (pinfunction "24_24") (pintype "bidirectional"))
    )
    (net (code "40") (name "LINEA5") (class "Default")
      (node (ref "QUANTUM_CONNECTOR") (pin "23") (pinfunction "23_23") (pintype "passive"))
      (node (ref "TEENSY3.2_2") (pin "27") (pinfunction "27/A16_27") (pintype "bidirectional"))
    )
    (net (code "41") (name "LINEA6") (class "Default")
      (node (ref "QUANTUM_CONNECTOR") (pin "16") (pinfunction "16_16") (pintype "passive"))
      (node (ref "TEENSY3.2_2") (pin "26") (pinfunction "26/A15_26") (pintype "bidirectional"))
    )
    (net (code "42") (name "LINEA7") (class "Default")
      (node (ref "QUANTUM_CONNECTOR") (pin "18") (pinfunction "18_18") (pintype "passive"))
      (node (ref "TEENSY3.2_2") (pin "14/A0") (pinfunction "14/A0_14/A0") (pintype "bidirectional"))
    )
    (net (code "43") (name "LINEA8") (class "Default")
      (node (ref "QUANTUM_CONNECTOR") (pin "20") (pinfunction "20_20") (pintype "passive"))
      (node (ref "TEENSY3.2_2") (pin "15/A1") (pinfunction "15/A1/T_15/A1") (pintype "bidirectional"))
    )
    (net (code "44") (name "LINEA9") (class "Default")
      (node (ref "QUANTUM_CONNECTOR") (pin "22") (pinfunction "22_22") (pintype "passive"))
      (node (ref "TEENSY3.2_2") (pin "16/A2") (pinfunction "16/A2/T_16/A2") (pintype "bidirectional"))
    )
    (net (code "45") (name "LINEAANT") (class "Default")
      (node (ref "QUANTUM_CONNECTOR") (pin "24") (pinfunction "24_24") (pintype "passive"))
      (node (ref "TEENSY3.2_2") (pin "33") (pinfunction "33/T_33") (pintype "bidirectional"))
    )
    (net (code "46") (name "MISO") (class "Default")
      (node (ref "SPI") (pin "1") (pinfunction "1_1") (pintype "passive"))
      (node (ref "TEENSY3.2_2") (pin "12") (pinfunction "12/MISO_12") (pintype "bidirectional"))
    )
    (net (code "47") (name "MOSI") (class "Default")
      (node (ref "DISPLAY1") (pin "SDA") (pinfunction "SDA_SDA") (pintype "bidirectional"))
      (node (ref "SPI") (pin "4") (pinfunction "4_4") (pintype "passive"))
      (node (ref "TEENSY3.2_2") (pin "11") (pinfunction "11/MOSI_11") (pintype "bidirectional"))
    )
    (net (code "48") (name "Net-(LED1-PadC)") (class "Default")
      (node (ref "LED1") (pin "C") (pinfunction "C_C") (pintype "passive"))
      (node (ref "R10") (pin "2") (pinfunction "2_2") (pintype "passive"))
    )
    (net (code "49") (name "Net-(LED2-PadC)") (class "Default")
      (node (ref "LED2") (pin "C") (pinfunction "C_C") (pintype "passive"))
      (node (ref "R1") (pin "2") (pinfunction "2_2") (pintype "passive"))
    )
    (net (code "50") (name "Net-(LED3-PadC)") (class "Default")
      (node (ref "LED3") (pin "C") (pinfunction "C_C") (pintype "passive"))
      (node (ref "R14") (pin "2") (pinfunction "2_2") (pintype "passive"))
    )
    (net (code "51") (name "Net-(LED4-PadC)") (class "Default")
      (node (ref "LED4") (pin "C") (pinfunction "C_C") (pintype "passive"))
      (node (ref "R13") (pin "2") (pinfunction "2_2") (pintype "passive"))
    )
    (net (code "52") (name "Net-(LED5-PadC)") (class "Default")
      (node (ref "LED5") (pin "C") (pinfunction "C_C") (pintype "passive"))
      (node (ref "R4") (pin "2") (pinfunction "2_2") (pintype "passive"))
    )
    (net (code "53") (name "Net-(LED6-PadC)") (class "Default")
      (node (ref "LED6") (pin "C") (pinfunction "C_C") (pintype "passive"))
      (node (ref "R11") (pin "2") (pinfunction "2_2") (pintype "passive"))
    )
    (net (code "54") (name "Net-(LED7-PadC)") (class "Default")
      (node (ref "LED7") (pin "C") (pinfunction "C_C") (pintype "passive"))
      (node (ref "R16") (pin "2") (pinfunction "2_2") (pintype "passive"))
    )
    (net (code "55") (name "Net-(LED8-PadC)") (class "Default")
      (node (ref "LED8") (pin "C") (pinfunction "C_C") (pintype "passive"))
      (node (ref "R17") (pin "2") (pinfunction "2_2") (pintype "passive"))
    )
    (net (code "56") (name "Net-(LED_3.3-PadC)") (class "Default")
      (node (ref "LED_3.3") (pin "C") (pinfunction "C_C") (pintype "passive"))
      (node (ref "R7") (pin "2") (pinfunction "2_2") (pintype "passive"))
    )
    (net (code "57") (name "Net-(LED_5-PadC)") (class "Default")
      (node (ref "LED_5") (pin "C") (pinfunction "C_C") (pintype "passive"))
      (node (ref "R3") (pin "2") (pinfunction "2_2") (pintype "passive"))
    )
    (net (code "58") (name "Net-(LED_RGB-BLUE_A)") (class "Default")
      (node (ref "LED_RGB") (pin "3") (pinfunction "BLUE_A_3") (pintype "bidirectional"))
      (node (ref "R5") (pin "1") (pinfunction "1_1") (pintype "passive"))
    )
    (net (code "59") (name "Net-(LED_RGB-GREEN_A)") (class "Default")
      (node (ref "LED_RGB") (pin "1") (pinfunction "GREEN_A_1") (pintype "bidirectional"))
      (node (ref "R8") (pin "1") (pinfunction "1_1") (pintype "passive"))
    )
    (net (code "60") (name "Net-(LED_RGB-RED_A)") (class "Default")
      (node (ref "LED_RGB") (pin "2") (pinfunction "RED_A_2") (pintype "bidirectional"))
      (node (ref "R9") (pin "1") (pinfunction "1_1") (pintype "passive"))
    )
    (net (code "61") (name "Net-(R6-Pad1)") (class "Default")
      (node (ref "R6") (pin "1") (pinfunction "1_1") (pintype "passive"))
      (node (ref "SW") (pin "5") (pinfunction "5_5") (pintype "passive"))
    )
    (net (code "62") (name "Net-(R62-Pad1)") (class "Default")
      (node (ref "R62") (pin "1") (pinfunction "1_1") (pintype "passive"))
      (node (ref "SW") (pin "8") (pinfunction "8_8") (pintype "passive"))
    )
    (net (code "63") (name "Net-(R63-Pad2)") (class "Default")
      (node (ref "R63") (pin "2") (pinfunction "2_2") (pintype "passive"))
      (node (ref "SW") (pin "7") (pinfunction "7_7") (pintype "passive"))
    )
    (net (code "64") (name "Net-(R64-Pad2)") (class "Default")
      (node (ref "R64") (pin "2") (pinfunction "2_2") (pintype "passive"))
      (node (ref "SW") (pin "6") (pinfunction "6_6") (pintype "passive"))
    )
    (net (code "65") (name "PALLA") (class "Default")
      (node (ref "QUANTUM_CONNECTOR") (pin "13") (pinfunction "13_13") (pintype "passive"))
      (node (ref "TEENSY3.2_2") (pin "28") (pinfunction "28/A17_28") (pintype "bidirectional"))
    )
    (net (code "66") (name "PROGRAM") (class "Default")
      (node (ref "PROGRAM") (pin "A2") (pinfunction "1_A2") (pintype "passive"))
      (node (ref "USB_2") (pin "5") (pinfunction "5_5") (pintype "passive"))
    )
    (net (code "67") (name "PULS") (class "Default")
      (node (ref "C57") (pin "2") (pinfunction "2_2") (pintype "passive"))
      (node (ref "ENCODER") (pin "B") (pinfunction "B_B") (pintype "passive"))
      (node (ref "TEENSY3.2_2") (pin "23/A9") (pinfunction "23/A9/T/PWM_23/A9") (pintype "bidirectional"))
    )
    (net (code "68") (name "PWM1") (class "Default")
      (node (ref "QUANTUM_CONNECTOR") (pin "4") (pinfunction "4_4") (pintype "passive"))
      (node (ref "TEENSY3.2_2") (pin "5") (pinfunction "5/PWM_5") (pintype "bidirectional"))
    )
    (net (code "69") (name "PWM2") (class "Default")
      (node (ref "QUANTUM_CONNECTOR") (pin "10") (pinfunction "10_10") (pintype "passive"))
      (node (ref "TEENSY3.2_2") (pin "9") (pinfunction "9/RX2/PWM_9") (pintype "bidirectional"))
    )
    (net (code "70") (name "PWM3") (class "Default")
      (node (ref "QUANTUM_CONNECTOR") (pin "9") (pinfunction "9_9") (pintype "passive"))
      (node (ref "TEENSY3.2_2") (pin "32") (pinfunction "32/T/PWM_32") (pintype "bidirectional"))
    )
    (net (code "71") (name "PWM4") (class "Default")
      (node (ref "QUANTUM_CONNECTOR") (pin "3") (pinfunction "3_3") (pintype "passive"))
      (node (ref "TEENSY3.2_2") (pin "4") (pinfunction "4/CAN-RX-PWM_4") (pintype "bidirectional"))
    )
    (net (code "72") (name "RED") (class "Default")
      (node (ref "R9") (pin "2") (pinfunction "2_2") (pintype "passive"))
      (node (ref "TEENSY3.2_2") (pin "20/A6") (pinfunction "20/A6/PWM_20/A6") (pintype "bidirectional"))
    )
    (net (code "73") (name "RESET") (class "Default")
      (node (ref "SPI") (pin "5") (pinfunction "5_5") (pintype "passive"))
    )
    (net (code "74") (name "SCK") (class "Default")
      (node (ref "DISPLAY1") (pin "SCK") (pinfunction "SCK_SCK") (pintype "bidirectional"))
      (node (ref "SPI") (pin "3") (pinfunction "3_3") (pintype "passive"))
      (node (ref "TEENSY3.2_2") (pin "13") (pinfunction "13/SCK/LED_13") (pintype "bidirectional"))
    )
    (net (code "75") (name "SCL") (class "Default")
      (node (ref "R65") (pin "1") (pinfunction "1_1") (pintype "passive"))
      (node (ref "TEENSY3.2_2") (pin "19/A5") (pinfunction "19/A5/T/SCL0_19/A5") (pintype "bidirectional"))
      (node (ref "U$5") (pin "SCL") (pinfunction "SCL_SCL") (pintype "bidirectional"))
    )
    (net (code "76") (name "SDA") (class "Default")
      (node (ref "R66") (pin "1") (pinfunction "1_1") (pintype "passive"))
      (node (ref "TEENSY3.2_2") (pin "18/A4") (pinfunction "18/A4/T/SDA0_18/A4") (pintype "bidirectional"))
      (node (ref "U$5") (pin "SDA") (pinfunction "SDA_SDA") (pintype "bidirectional"))
    )
    (net (code "77") (name "SEL") (class "Default")
      (node (ref "ENCODER") (pin "E") (pinfunction "2_E") (pintype "passive"))
      (node (ref "TEENSY3.2_2") (pin "A11") (pinfunction "A11_A11") (pintype "bidirectional"))
    )
    (net (code "78") (name "SOLENOIDE") (class "Default")
      (node (ref "QUANTUM_CONNECTOR") (pin "14") (pinfunction "14_14") (pintype "passive"))
      (node (ref "TEENSY3.2_2") (pin "29") (pinfunction "29/A18/SCL1_29") (pintype "bidirectional"))
    )
    (net (code "79") (name "SPEED") (class "Default")
      (node (ref "R12") (pin "S") (pinfunction "S_S") (pintype "passive"))
      (node (ref "TEENSY3.2_2") (pin "A12") (pinfunction "A12_A12") (pintype "bidirectional"))
    )
    (net (code "80") (name "TEENSY1-RX_TEENSY2-TX") (class "Default")
      (node (ref "QUANTUM_CONNECTOR") (pin "29") (pinfunction "29_29") (pintype "passive"))
      (node (ref "TEENSY3.2_2") (pin "1") (pinfunction "1/TX1/T_1") (pintype "bidirectional"))
    )
    (net (code "81") (name "TEENSY1-TX_TEENSY2-RX") (class "Default")
      (node (ref "QUANTUM_CONNECTOR") (pin "30") (pinfunction "30_30") (pintype "passive"))
      (node (ref "TEENSY3.2_2") (pin "0") (pinfunction "0/RX1/T_0") (pintype "bidirectional"))
    )
    (net (code "82") (name "TONE") (class "Default")
      (node (ref "BUZZER") (pin "+") (pinfunction "1_+") (pintype "passive"))
      (node (ref "TEENSY3.2_2") (pin "RESET/DAC") (pinfunction "A14/DAC_RESET/DAC") (pintype "bidirectional"))
    )
    (net (code "83") (name "VBATTEENSY") (class "Default")
      (node (ref "TEENSY3.2_2") (pin "VBAT") (pinfunction "VBAT_VBAT") (pintype "power_in"))
    )
    (net (code "84") (name "VIN") (class "Default")
      (node (ref "TEENSY3.2_2") (pin "VIN") (pinfunction "VIN_VIN") (pintype "power_in"))
    )
    (net (code "85") (name "VUSB") (class "Default")
      (node (ref "USB") (pin "VBUS") (pinfunction "VBUS_VBUS") (pintype "bidirectional"))
      (node (ref "USB_2") (pin "1") (pinfunction "1_1") (pintype "passive"))
    )
    (net (code "86") (name "unconnected-(IC2-QH*-Pad9)") (class "Default")
      (node (ref "IC2") (pin "9") (pinfunction "QH*_9") (pintype "tri_state"))
    )
    (net (code "87") (name "unconnected-(TEENSY3.2_2-PadPGM)") (class "Default")
      (node (ref "TEENSY3.2_2") (pin "PGM") (pinfunction "PGM_PGM") (pintype "bidirectional"))
    )
    (net (code "88") (name "unconnected-(TEENSY3.2_2-PadVUSB)") (class "Default")
      (node (ref "TEENSY3.2_2") (pin "VUSB") (pinfunction "VUSB_VUSB") (pintype "power_in"))
    )
    (net (code "89") (name "unconnected-(U$9-PadCS_I)") (class "Default")
      (node (ref "U$9") (pin "CS_I") (pinfunction "CS_I_CS_I") (pintype "no_connect"))
    )
    (net (code "90") (name "unconnected-(U$9-PadRST)") (class "Default")
      (node (ref "U$9") (pin "RST") (pinfunction "RST_RST") (pintype "no_connect"))
    )
  )
)
